# usb_ft231.net
KiCad netlist of a schematic drawn in Altium Designer
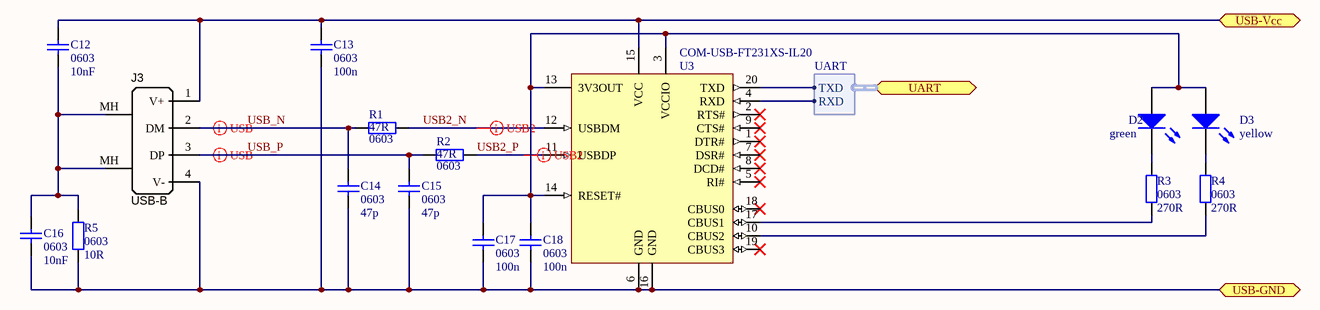
[diagram p0: usb_ft231.SchDoc]

(export (version "E")
  (design (tool "Eeschema 10.0.6"))
  (components
    (comp (ref "C12")
      (value "0603")
      (footprint "SMD_Capacitor_0603")
      (description "Capacitor")
      (fields (field (name "ALTIUM_VALUE") "10nF") (field (name "PUBLISHER") "Altium Limited"))
      (libsource (lib "Miscellaneous Devices") (part "Cap"))
    )
    (comp (ref "C13")
      (value "0603")
      (footprint "SMD_Capacitor_0603")
      (description "Capacitor")
      (fields (field (name "ALTIUM_VALUE") "100n") (field (name "PUBLISHER") "Altium Limited"))
      (libsource (lib "Miscellaneous Devices") (part "Cap"))
    )
    (comp (ref "C14")
      (value "0603")
      (footprint "SMD_Capacitor_0603")
      (description "Capacitor")
      (fields (field (name "ALTIUM_VALUE") "47p") (field (name "PUBLISHER") "Altium Limited"))
      (libsource (lib "Miscellaneous Devices") (part "Cap"))
    )
    (comp (ref "C15")
      (value "0603")
      (footprint "SMD_Capacitor_0603")
      (description "Capacitor")
      (fields (field (name "ALTIUM_VALUE") "47p") (field (name "PUBLISHER") "Altium Limited"))
      (libsource (lib "Miscellaneous Devices") (part "Cap"))
    )
    (comp (ref "C16")
      (value "0603")
      (footprint "SMD_Capacitor_0603")
      (description "Capacitor")
      (fields (field (name "ALTIUM_VALUE") "10nF") (field (name "PUBLISHER") "Altium Limited"))
      (libsource (lib "Miscellaneous Devices") (part "Cap"))
    )
    (comp (ref "C17")
      (value "0603")
      (footprint "SMD_Capacitor_0603")
      (description "Capacitor")
      (fields (field (name "ALTIUM_VALUE") "100n") (field (name "PUBLISHER") "Altium Limited"))
      (libsource (lib "Miscellaneous Devices") (part "Cap"))
    )
    (comp (ref "C18")
      (value "0603")
      (footprint "SMD_Capacitor_0603")
      (description "Capacitor")
      (fields (field (name "ALTIUM_VALUE") "100n") (field (name "PUBLISHER") "Altium Limited"))
      (libsource (lib "Miscellaneous Devices") (part "Cap"))
    )
    (comp (ref "D2")
      (value "green")
      (footprint "LED 0805 GREEN")
      (description "Typical RED, GREEN, YELLOW, AMBER GaAs LED")
      (fields (field (name "PUBLISHER") "Altium Limited"))
      (libsource (lib "Miscellaneous Devices") (part "LED2"))
    )
    (comp (ref "D3")
      (value "yellow")
      (footprint "LED 0805 Yellow")
      (description "Typical RED, GREEN, YELLOW, AMBER GaAs LED")
      (fields (field (name "PUBLISHER") "Altium Limited"))
      (libsource (lib "Miscellaneous Devices") (part "LED2"))
    )
    (comp (ref "J3")
      (value "USB-B")
      (footprint "USB_TypeB_Tyco")
      (description "Connector THT Type B USB connector")
      (libsource (lib "PBL - Connectors") (part "USB_TypeB"))
    )
    (comp (ref "R1")
      (value "0603")
      (footprint "SMD_Resistor_0603")
      (description "Resistor")
      (fields (field (name "ALTIUM_VALUE") "47R") (field (name "PUBLISHER") "Altium Limited"))
      (libsource (lib "") (part "Res2_1"))
    )
    (comp (ref "R2")
      (value "0603")
      (footprint "SMD_Resistor_0603")
      (description "Resistor")
      (fields (field (name "ALTIUM_VALUE") "47R") (field (name "PUBLISHER") "Altium Limited"))
      (libsource (lib "") (part "Res2_1"))
    )
    (comp (ref "R3")
      (value "0603")
      (footprint "SMD_Resistor_0603")
      (description "Resistor")
      (fields (field (name "ALTIUM_VALUE") "270R") (field (name "PUBLISHER") "Altium Limited"))
      (libsource (lib "Miscellaneous Devices") (part "Res2"))
    )
    (comp (ref "R4")
      (value "0603")
      (footprint "SMD_Resistor_0603")
      (description "Resistor")
      (fields (field (name "ALTIUM_VALUE") "270R") (field (name "PUBLISHER") "Altium Limited"))
      (libsource (lib "Miscellaneous Devices") (part "Res2"))
    )
    (comp (ref "R5")
      (value "0603")
      (footprint "SMD_Resistor_0603")
      (description "Resistor")
      (fields (field (name "ALTIUM_VALUE") "10R") (field (name "PUBLISHER") "Altium Limited"))
      (libsource (lib "Miscellaneous Devices") (part "Res2"))
    )
    (comp (ref "U3")
      (value "COM-USB-FT231XS-IL20")
      (footprint "SSOP-20_L")
      (libsource (lib "altium-import") (part "root_0_COM-USB-FT231XS-IL20_"))
    )
  )
  (nets
    (net (code "2") (name "/RXD") (class "Default")
      (node (ref "U3") (pin "4") (pinfunction "RXD_4") (pintype "input"))
    )
    (net (code "3") (name "/TXD") (class "Default")
      (node (ref "U3") (pin "20") (pinfunction "TXD_20") (pintype "output"))
    )
    (net (code "4") (name "/USB-GND") (class "Default")
      (node (ref "C13") (pin "2") (pinfunction "2_2") (pintype "passive"))
      (node (ref "C14") (pin "1") (pinfunction "1_1") (pintype "passive"))
      (node (ref "C15") (pin "1") (pinfunction "1_1") (pintype "passive"))
      (node (ref "C16") (pin "2") (pinfunction "2_2") (pintype "passive"))
      (node (ref "C17") (pin "2") (pinfunction "2_2") (pintype "passive"))
      (node (ref "C18") (pin "1") (pinfunction "1_1") (pintype "passive"))
      (node (ref "J3") (pin "4") (pinfunction "V-_4") (pintype "passive"))
      (node (ref "R5") (pin "1") (pinfunction "1_1") (pintype "passive"))
      (node (ref "U3") (pin "16") (pinfunction "GND_16") (pintype "power_in"))
      (node (ref "U3") (pin "6") (pinfunction "GND_6") (pintype "power_in"))
    )
    (net (code "5") (name "/USB-Vcc") (class "Default")
      (node (ref "C12") (pin "1") (pinfunction "1_1") (pintype "passive"))
      (node (ref "C13") (pin "1") (pinfunction "1_1") (pintype "passive"))
      (node (ref "J3") (pin "1") (pinfunction "V+_1") (pintype "passive"))
      (node (ref "U3") (pin "15") (pinfunction "VCC_15") (pintype "power_in"))
    )
    (net (code "6") (name "/USB2_N") (class "Default")
      (node (ref "R1") (pin "2") (pinfunction "2_2") (pintype "passive"))
      (node (ref "U3") (pin "12") (pinfunction "USBDM_12") (pintype "input"))
    )
    (net (code "7") (name "/USB2_P") (class "Default")
      (node (ref "R2") (pin "2") (pinfunction "2_2") (pintype "passive"))
      (node (ref "U3") (pin "11") (pinfunction "USBDP_11") (pintype "input"))
    )
    (net (code "8") (name "/USB_N") (class "Default")
      (node (ref "C14") (pin "2") (pinfunction "2_2") (pintype "passive"))
      (node (ref "J3") (pin "2") (pinfunction "DM_2") (pintype "passive"))
      (node (ref "R1") (pin "1") (pinfunction "1_1") (pintype "passive"))
    )
    (net (code "9") (name "/USB_P") (class "Default")
      (node (ref "C15") (pin "2") (pinfunction "2_2") (pintype "passive"))
      (node (ref "J3") (pin "3") (pinfunction "DP_3") (pintype "passive"))
      (node (ref "R2") (pin "1") (pinfunction "1_1") (pintype "passive"))
    )
    (net (code "11") (name "Net-(D2-A)") (class "Default")
      (node (ref "C17") (pin "1") (pinfunction "1_1") (pintype "passive"))
      (node (ref "C18") (pin "2") (pinfunction "2_2") (pintype "passive"))
      (node (ref "D2") (pin "1") (pinfunction "A_1") (pintype "passive"))
      (node (ref "D3") (pin "1") (pinfunction "A_1") (pintype "passive"))
      (node (ref "U3") (pin "13") (pinfunction "3V3OUT_13") (pintype "power_in"))
      (node (ref "U3") (pin "14") (pinfunction "RESET#_14") (pintype "input"))
      (node (ref "U3") (pin "3") (pinfunction "VCCIO_3") (pintype "power_in"))
    )
    (net (code "12") (name "Net-(D2-K)") (class "Default")
      (node (ref "D2") (pin "2") (pinfunction "K_2") (pintype "passive"))
      (node (ref "R3") (pin "2") (pinfunction "2_2") (pintype "passive"))
    )
    (net (code "13") (name "Net-(D3-K)") (class "Default")
      (node (ref "D3") (pin "2") (pinfunction "K_2") (pintype "passive"))
      (node (ref "R4") (pin "2") (pinfunction "2_2") (pintype "passive"))
    )
    (net (code "14") (name "Net-(J3-Shell)") (class "Default")
      (node (ref "C12") (pin "2") (pinfunction "2_2") (pintype "passive"))
      (node (ref "C16") (pin "1") (pinfunction "1_1") (pintype "passive"))
      (node (ref "J3") (pin "MH") (pinfunction "Shell_MH") (pintype "passive"))
      (node (ref "R5") (pin "2") (pinfunction "2_2") (pintype "passive"))
    )
    (net (code "15") (name "Net-(U3-CBUS1)") (class "Default")
      (node (ref "R3") (pin "1") (pinfunction "1_1") (pintype "passive"))
      (node (ref "U3") (pin "17") (pinfunction "CBUS1_17") (pintype "bidirectional"))
    )
    (net (code "16") (name "Net-(U3-CBUS2)") (class "Default")
      (node (ref "R4") (pin "1") (pinfunction "1_1") (pintype "passive"))
      (node (ref "U3") (pin "10") (pinfunction "CBUS2_10") (pintype "bidirectional"))
    )
    (net (code "17") (name "unconnected-(U3-CBUS0-Pad18)") (class "Default")
      (node (ref "U3") (pin "18") (pinfunction "CBUS0_18") (pintype "bidirectional+no_connect"))
    )
    (net (code "18") (name "unconnected-(U3-CBUS3-Pad19)") (class "Default")
      (node (ref "U3") (pin "19") (pinfunction "CBUS3_19") (pintype "bidirectional+no_connect"))
    )
    (net (code "19") (name "unconnected-(U3-CTS#-Pad9)") (class "Default")
      (node (ref "U3") (pin "9") (pinfunction "CTS#_9") (pintype "input+no_connect"))
    )
    (net (code "20") (name "unconnected-(U3-DCD#-Pad8)") (class "Default")
      (node (ref "U3") (pin "8") (pinfunction "DCD#_8") (pintype "input+no_connect"))
    )
    (net (code "21") (name "unconnected-(U3-DSR#-Pad7)") (class "Default")
      (node (ref "U3") (pin "7") (pinfunction "DSR#_7") (pintype "input+no_connect"))
    )
    (net (code "22") (name "unconnected-(U3-DTR#-Pad1)") (class "Default")
      (node (ref "U3") (pin "1") (pinfunction "DTR#_1") (pintype "output+no_connect"))
    )
    (net (code "23") (name "unconnected-(U3-RI#-Pad5)") (class "Default")
      (node (ref "U3") (pin "5") (pinfunction "RI#_5") (pintype "input+no_connect"))
    )
    (net (code "24") (name "unconnected-(U3-RTS#-Pad2)") (class "Default")
      (node (ref "U3") (pin "2") (pinfunction "RTS#_2") (pintype "output+no_connect"))
    )
  )
)
